# DUE_Shield.net
KiCad netlist of a schematic drawn in Altium Designer
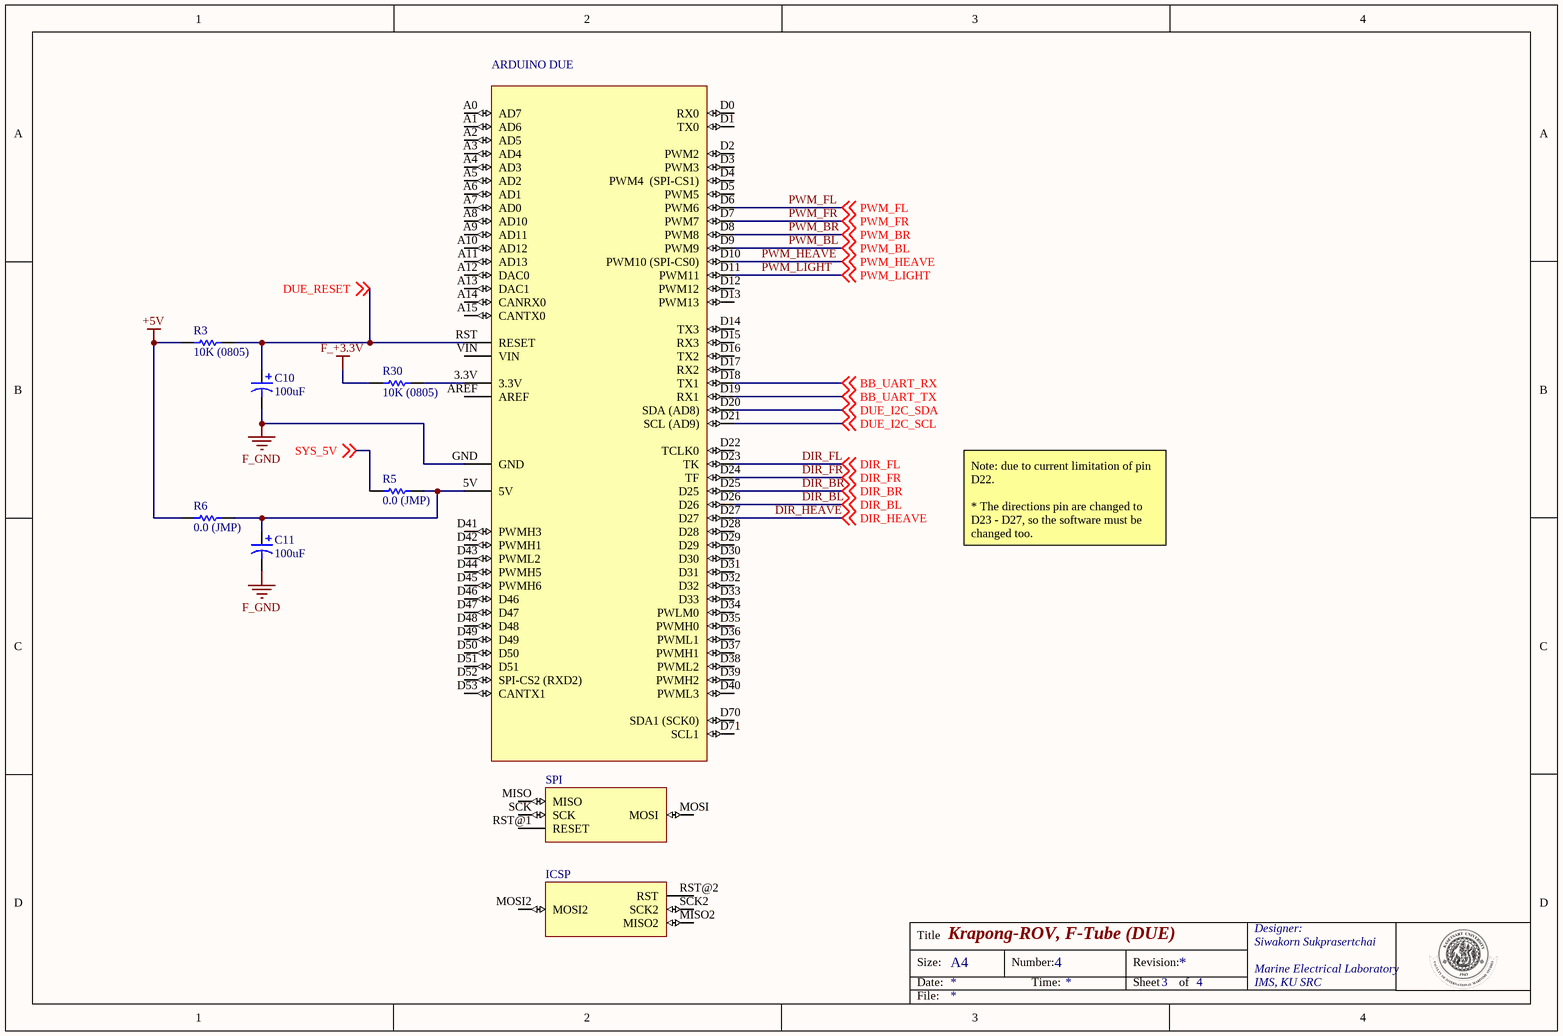
[diagram p0: DUE_Shield.SchDoc]

(export (version "E")
  (design (tool "Eeschema 10.0.6"))
  (components
    (comp (ref "C10")
      (value "100uF")
      (footprint "PCB-ec5i0bi6g8n3i6bd77c9-1")
      (description "WX Series 100 uF 25 V ±20 % Surface Mount Chip Aluminum Electrolytic Capacitor")
      (fields (field (name "MANUFACTURER PART NUMBER") "UWX1E101MCL1GB"))
      (libsource (lib "FavoritesLibrary") (part "SYM-42da8bd37ecc9d1d-1"))
    )
    (comp (ref "C11")
      (value "100uF")
      (footprint "PCB-ibkib54e90xysjsqnert-1")
      (description "Capacitor Alum Elec, 10uf, 100v, 20%, Capacitor Alum Elec, 10uf, 100v, 20%, Smd, Full Reel")
      (fields (field (name "MANUFACTURER PART NUMBER") "EEE-2AA100UP"))
      (libsource (lib "FavoritesLibrary") (part "SYM-da8810cd3d6e054f-1"))
    )
    (comp (ref "DUE")
      (value "arduino due schematic and base pcb to top")
      (footprint "PCB-973053-1")
      (description "ARDUINO DUE schematic and base pcb")
      (libsource (lib "CommunityVault") (part "CMP-973053-32"))
    )
    (comp (ref "R3")
      (value "10K (0805)")
      (footprint "RESC2013X60X40NL15T20")
      (description "RES SMD 10K OHM 1% 1/3W 0805")
      (libsource (lib "CommunityVault") (part "CMP-1860549-2"))
    )
    (comp (ref "R5")
      (value "0.0 (JMP)")
      (footprint "RESC2013X60X35ML10T20")
      (description "Res Thick Film 0805 0 Ohm Molded SMD Paper T/R")
      (fields (field (name "MANUFACTURER PART NUMBER") "RC0805FR-070RL"))
      (libsource (lib "FavoritesLibrary") (part "SYM-f3d13a5618eb2c16-1"))
    )
    (comp (ref "R6")
      (value "0.0 (JMP)")
      (footprint "RESC2013X60X35ML10T20")
      (description "Res Thick Film 0805 0 Ohm Molded SMD Paper T/R")
      (fields (field (name "MANUFACTURER PART NUMBER") "RC0805FR-070RL"))
      (libsource (lib "FavoritesLibrary") (part "SYM-f3d13a5618eb2c16-1"))
    )
    (comp (ref "R30")
      (value "10K (0805)")
      (footprint "RESC2013X60X40NL15T20")
      (description "RES SMD 10K OHM 1% 1/3W 0805")
      (libsource (lib "FavoritesLibrary") (part "RES-2"))
    )
  )
  (nets
    (net (code "1") (name "+5V") (class "Default")
      (node (ref "R3") (pin "1") (pinfunction "1_1") (pintype "passive"))
      (node (ref "R6") (pin "1") (pinfunction "1_1") (pintype "passive"))
    )
    (net (code "2") (name "BB_UART_RX") (class "Default")
      (node (ref "DUE") (pin "D18") (pinfunction "TX1_D18") (pintype "bidirectional"))
    )
    (net (code "3") (name "BB_UART_TX") (class "Default")
      (node (ref "DUE") (pin "D19") (pinfunction "RX1_D19") (pintype "bidirectional"))
    )
    (net (code "4") (name "DIR_BL") (class "Default")
      (node (ref "DUE") (pin "D26") (pinfunction "D26_D26") (pintype "bidirectional"))
    )
    (net (code "5") (name "DIR_BR") (class "Default")
      (node (ref "DUE") (pin "D25") (pinfunction "D25_D25") (pintype "bidirectional"))
    )
    (net (code "6") (name "DIR_FL") (class "Default")
      (node (ref "DUE") (pin "D23") (pinfunction "TK_D23") (pintype "bidirectional"))
    )
    (net (code "7") (name "DIR_FR") (class "Default")
      (node (ref "DUE") (pin "D24") (pinfunction "TF_D24") (pintype "bidirectional"))
    )
    (net (code "8") (name "DIR_HEAVE") (class "Default")
      (node (ref "DUE") (pin "D27") (pinfunction "D27_D27") (pintype "bidirectional"))
    )
    (net (code "9") (name "DUE_I2C_SCL") (class "Default")
      (node (ref "DUE") (pin "D21") (pinfunction "SCL_(AD9)_D21") (pintype "bidirectional"))
    )
    (net (code "10") (name "DUE_I2C_SDA") (class "Default")
      (node (ref "DUE") (pin "D20") (pinfunction "SDA_(AD8)_D20") (pintype "bidirectional"))
    )
    (net (code "11") (name "DUE_RESET") (class "Default")
      (node (ref "C10") (pin "1") (pinfunction "1_1") (pintype "passive"))
      (node (ref "DUE") (pin "RST") (pinfunction "RESET_RST") (pintype "passive"))
      (node (ref "R3") (pin "2") (pinfunction "2_2") (pintype "passive"))
    )
    (net (code "12") (name "F_+3.3V") (class "Default")
      (node (ref "R30") (pin "1") (pinfunction "1_1") (pintype "passive"))
    )
    (net (code "13") (name "F_GND") (class "Default")
      (node (ref "C10") (pin "2") (pinfunction "2_2") (pintype "passive"))
      (node (ref "C11") (pin "2") (pinfunction "2_2") (pintype "passive"))
      (node (ref "DUE") (pin "GND") (pinfunction "GND_GND") (pintype "power_in"))
    )
    (net (code "14") (name "Net-(C11-Pad1)") (class "Default")
      (node (ref "C11") (pin "1") (pinfunction "1_1") (pintype "passive"))
      (node (ref "DUE") (pin "5V") (pinfunction "5V_5V") (pintype "power_in"))
      (node (ref "R5") (pin "2") (pinfunction "2_2") (pintype "passive"))
      (node (ref "R6") (pin "2") (pinfunction "2_2") (pintype "passive"))
    )
    (net (code "15") (name "Net-(DUE-Pad3.3V)") (class "Default")
      (node (ref "DUE") (pin "3.3V") (pinfunction "3.3V_3.3V") (pintype "power_in"))
      (node (ref "R30") (pin "2") (pinfunction "2_2") (pintype "passive"))
    )
    (net (code "16") (name "PWM_BL") (class "Default")
      (node (ref "DUE") (pin "D9") (pinfunction "PWM9_D9") (pintype "bidirectional"))
    )
    (net (code "17") (name "PWM_BR") (class "Default")
      (node (ref "DUE") (pin "D8") (pinfunction "PWM8_D8") (pintype "bidirectional"))
    )
    (net (code "18") (name "PWM_FL") (class "Default")
      (node (ref "DUE") (pin "D6") (pinfunction "PWM6_D6") (pintype "bidirectional"))
    )
    (net (code "19") (name "PWM_FR") (class "Default")
      (node (ref "DUE") (pin "D7") (pinfunction "PWM7_D7") (pintype "bidirectional"))
    )
    (net (code "20") (name "PWM_HEAVE") (class "Default")
      (node (ref "DUE") (pin "D10") (pinfunction "PWM10_(SPI-CS0)_D10") (pintype "bidirectional"))
    )
    (net (code "21") (name "PWM_LIGHT") (class "Default")
      (node (ref "DUE") (pin "D11") (pinfunction "PWM11_D11") (pintype "bidirectional"))
    )
    (net (code "22") (name "SYS_5V") (class "Default")
      (node (ref "R5") (pin "1") (pinfunction "1_1") (pintype "passive"))
    )
    (net (code "23") (name "unconnected-(DUE-AD0-PadA7)") (class "Default")
      (node (ref "DUE") (pin "A7") (pinfunction "AD0_A7") (pintype "bidirectional"))
    )
    (net (code "24") (name "unconnected-(DUE-AD1-PadA6)") (class "Default")
      (node (ref "DUE") (pin "A6") (pinfunction "AD1_A6") (pintype "bidirectional"))
    )
    (net (code "25") (name "unconnected-(DUE-AD2-PadA5)") (class "Default")
      (node (ref "DUE") (pin "A5") (pinfunction "AD2_A5") (pintype "bidirectional"))
    )
    (net (code "26") (name "unconnected-(DUE-AD3-PadA4)") (class "Default")
      (node (ref "DUE") (pin "A4") (pinfunction "AD3_A4") (pintype "bidirectional"))
    )
    (net (code "27") (name "unconnected-(DUE-AD4-PadA3)") (class "Default")
      (node (ref "DUE") (pin "A3") (pinfunction "AD4_A3") (pintype "bidirectional"))
    )
    (net (code "28") (name "unconnected-(DUE-AD5-PadA2)") (class "Default")
      (node (ref "DUE") (pin "A2") (pinfunction "AD5_A2") (pintype "bidirectional"))
    )
    (net (code "29") (name "unconnected-(DUE-AD6-PadA1)") (class "Default")
      (node (ref "DUE") (pin "A1") (pinfunction "AD6_A1") (pintype "bidirectional"))
    )
    (net (code "30") (name "unconnected-(DUE-AD7-PadA0)") (class "Default")
      (node (ref "DUE") (pin "A0") (pinfunction "AD7_A0") (pintype "bidirectional"))
    )
    (net (code "31") (name "unconnected-(DUE-AD10-PadA8)") (class "Default")
      (node (ref "DUE") (pin "A8") (pinfunction "AD10_A8") (pintype "bidirectional"))
    )
    (net (code "32") (name "unconnected-(DUE-AD11-PadA9)") (class "Default")
      (node (ref "DUE") (pin "A9") (pinfunction "AD11_A9") (pintype "bidirectional"))
    )
    (net (code "33") (name "unconnected-(DUE-AD12-PadA10)") (class "Default")
      (node (ref "DUE") (pin "A10") (pinfunction "AD12_A10") (pintype "bidirectional"))
    )
    (net (code "34") (name "unconnected-(DUE-AD13-PadA11)") (class "Default")
      (node (ref "DUE") (pin "A11") (pinfunction "AD13_A11") (pintype "bidirectional"))
    )
    (net (code "35") (name "unconnected-(DUE-CANRX0-PadA14)") (class "Default")
      (node (ref "DUE") (pin "A14") (pinfunction "CANRX0_A14") (pintype "bidirectional"))
    )
    (net (code "36") (name "unconnected-(DUE-CANTX0-PadA15)") (class "Default")
      (node (ref "DUE") (pin "A15") (pinfunction "CANTX0_A15") (pintype "bidirectional"))
    )
    (net (code "37") (name "unconnected-(DUE-CANTX1-PadD53)") (class "Default")
      (node (ref "DUE") (pin "D53") (pinfunction "CANTX1_D53") (pintype "bidirectional"))
    )
    (net (code "38") (name "unconnected-(DUE-DAC0-PadA12)") (class "Default")
      (node (ref "DUE") (pin "A12") (pinfunction "DAC0_A12") (pintype "bidirectional"))
    )
    (net (code "39") (name "unconnected-(DUE-DAC1-PadA13)") (class "Default")
      (node (ref "DUE") (pin "A13") (pinfunction "DAC1_A13") (pintype "bidirectional"))
    )
    (net (code "40") (name "unconnected-(DUE-PWLM0-PadD34)") (class "Default")
      (node (ref "DUE") (pin "D34") (pinfunction "PWLM0_D34") (pintype "bidirectional"))
    )
    (net (code "41") (name "unconnected-(DUE-PWM2-PadD2)") (class "Default")
      (node (ref "DUE") (pin "D2") (pinfunction "PWM2_D2") (pintype "bidirectional"))
    )
    (net (code "42") (name "unconnected-(DUE-PWM3-PadD3)") (class "Default")
      (node (ref "DUE") (pin "D3") (pinfunction "PWM3_D3") (pintype "bidirectional"))
    )
    (net (code "43") (name "unconnected-(DUE-PWM4__(SPI-CS1)-PadD4)") (class "Default")
      (node (ref "DUE") (pin "D4") (pinfunction "PWM4__(SPI-CS1)_D4") (pintype "bidirectional"))
    )
    (net (code "44") (name "unconnected-(DUE-PWM5-PadD5)") (class "Default")
      (node (ref "DUE") (pin "D5") (pinfunction "PWM5_D5") (pintype "bidirectional"))
    )
    (net (code "45") (name "unconnected-(DUE-PWM12-PadD12)") (class "Default")
      (node (ref "DUE") (pin "D12") (pinfunction "PWM12_D12") (pintype "bidirectional"))
    )
    (net (code "46") (name "unconnected-(DUE-PWM13-PadD13)") (class "Default")
      (node (ref "DUE") (pin "D13") (pinfunction "PWM13_D13") (pintype "bidirectional"))
    )
    (net (code "47") (name "unconnected-(DUE-PWMH0-PadD35)") (class "Default")
      (node (ref "DUE") (pin "D35") (pinfunction "PWMH0_D35") (pintype "bidirectional"))
    )
    (net (code "48") (name "unconnected-(DUE-PWMH1-PadD37)") (class "Default")
      (node (ref "DUE") (pin "D37") (pinfunction "PWMH1_D37") (pintype "bidirectional"))
    )
    (net (code "49") (name "unconnected-(DUE-PWMH1-PadD42)") (class "Default")
      (node (ref "DUE") (pin "D42") (pinfunction "PWMH1_D42") (pintype "bidirectional"))
    )
    (net (code "50") (name "unconnected-(DUE-PWMH2-PadD39)") (class "Default")
      (node (ref "DUE") (pin "D39") (pinfunction "PWMH2_D39") (pintype "bidirectional"))
    )
    (net (code "51") (name "unconnected-(DUE-PWMH3-PadD41)") (class "Default")
      (node (ref "DUE") (pin "D41") (pinfunction "PWMH3_D41") (pintype "bidirectional"))
    )
    (net (code "52") (name "unconnected-(DUE-PWMH5-PadD44)") (class "Default")
      (node (ref "DUE") (pin "D44") (pinfunction "PWMH5_D44") (pintype "bidirectional"))
    )
    (net (code "53") (name "unconnected-(DUE-PWMH6-PadD45)") (class "Default")
      (node (ref "DUE") (pin "D45") (pinfunction "PWMH6_D45") (pintype "bidirectional"))
    )
    (net (code "54") (name "unconnected-(DUE-PWML1-PadD36)") (class "Default")
      (node (ref "DUE") (pin "D36") (pinfunction "PWML1_D36") (pintype "bidirectional"))
    )
    (net (code "55") (name "unconnected-(DUE-PWML2-PadD38)") (class "Default")
      (node (ref "DUE") (pin "D38") (pinfunction "PWML2_D38") (pintype "bidirectional"))
    )
    (net (code "56") (name "unconnected-(DUE-PWML2-PadD43)") (class "Default")
      (node (ref "DUE") (pin "D43") (pinfunction "PWML2_D43") (pintype "bidirectional"))
    )
    (net (code "57") (name "unconnected-(DUE-PWML3-PadD40)") (class "Default")
      (node (ref "DUE") (pin "D40") (pinfunction "PWML3_D40") (pintype "bidirectional"))
    )
    (net (code "58") (name "unconnected-(DUE-PadAREF)") (class "Default")
      (node (ref "DUE") (pin "AREF") (pinfunction "AREF_AREF") (pintype "power_in"))
    )
    (net (code "59") (name "unconnected-(DUE-PadD28)") (class "Default")
      (node (ref "DUE") (pin "D28") (pinfunction "D28_D28") (pintype "bidirectional"))
    )
    (net (code "60") (name "unconnected-(DUE-PadD29)") (class "Default")
      (node (ref "DUE") (pin "D29") (pinfunction "D29_D29") (pintype "bidirectional"))
    )
    (net (code "61") (name "unconnected-(DUE-PadD30)") (class "Default")
      (node (ref "DUE") (pin "D30") (pinfunction "D30_D30") (pintype "bidirectional"))
    )
    (net (code "62") (name "unconnected-(DUE-PadD31)") (class "Default")
      (node (ref "DUE") (pin "D31") (pinfunction "D31_D31") (pintype "bidirectional"))
    )
    (net (code "63") (name "unconnected-(DUE-PadD32)") (class "Default")
      (node (ref "DUE") (pin "D32") (pinfunction "D32_D32") (pintype "bidirectional"))
    )
    (net (code "64") (name "unconnected-(DUE-PadD33)") (class "Default")
      (node (ref "DUE") (pin "D33") (pinfunction "D33_D33") (pintype "bidirectional"))
    )
    (net (code "65") (name "unconnected-(DUE-PadD46)") (class "Default")
      (node (ref "DUE") (pin "D46") (pinfunction "D46_D46") (pintype "bidirectional"))
    )
    (net (code "66") (name "unconnected-(DUE-PadD47)") (class "Default")
      (node (ref "DUE") (pin "D47") (pinfunction "D47_D47") (pintype "bidirectional"))
    )
    (net (code "67") (name "unconnected-(DUE-PadD48)") (class "Default")
      (node (ref "DUE") (pin "D48") (pinfunction "D48_D48") (pintype "bidirectional"))
    )
    (net (code "68") (name "unconnected-(DUE-PadD49)") (class "Default")
      (node (ref "DUE") (pin "D49") (pinfunction "D49_D49") (pintype "bidirectional"))
    )
    (net (code "69") (name "unconnected-(DUE-PadD50)") (class "Default")
      (node (ref "DUE") (pin "D50") (pinfunction "D50_D50") (pintype "bidirectional"))
    )
    (net (code "70") (name "unconnected-(DUE-PadD51)") (class "Default")
      (node (ref "DUE") (pin "D51") (pinfunction "D51_D51") (pintype "bidirectional"))
    )
    (net (code "71") (name "unconnected-(DUE-PadMISO)") (class "Default")
      (node (ref "DUE") (pin "MISO") (pinfunction "MISO_MISO") (pintype "bidirectional"))
    )
    (net (code "72") (name "unconnected-(DUE-PadMISO2)") (class "Default")
      (node (ref "DUE") (pin "MISO2") (pinfunction "MISO2_MISO2") (pintype "bidirectional"))
    )
    (net (code "73") (name "unconnected-(DUE-PadMOSI)") (class "Default")
      (node (ref "DUE") (pin "MOSI") (pinfunction "MOSI_MOSI") (pintype "bidirectional"))
    )
    (net (code "74") (name "unconnected-(DUE-PadMOSI2)") (class "Default")
      (node (ref "DUE") (pin "MOSI2") (pinfunction "MOSI2_MOSI2") (pintype "bidirectional"))
    )
    (net (code "75") (name "unconnected-(DUE-PadSCK)") (class "Default")
      (node (ref "DUE") (pin "SCK") (pinfunction "SCK_SCK") (pintype "bidirectional"))
    )
    (net (code "76") (name "unconnected-(DUE-PadSCK2)") (class "Default")
      (node (ref "DUE") (pin "SCK2") (pinfunction "SCK2_SCK2") (pintype "bidirectional"))
    )
    (net (code "77") (name "unconnected-(DUE-PadVIN)") (class "Default")
      (node (ref "DUE") (pin "VIN") (pinfunction "VIN_VIN") (pintype "power_in"))
    )
    (net (code "78") (name "unconnected-(DUE-RESET-PadRST@1)") (class "Default")
      (node (ref "DUE") (pin "RST@1") (pinfunction "RESET_RST@1") (pintype "passive"))
    )
    (net (code "79") (name "unconnected-(DUE-RST-PadRST@2)") (class "Default")
      (node (ref "DUE") (pin "RST@2") (pinfunction "RST_RST@2") (pintype "passive"))
    )
    (net (code "80") (name "unconnected-(DUE-RX0-PadD0)") (class "Default")
      (node (ref "DUE") (pin "D0") (pinfunction "RX0_D0") (pintype "bidirectional"))
    )
    (net (code "81") (name "unconnected-(DUE-RX2-PadD17)") (class "Default")
      (node (ref "DUE") (pin "D17") (pinfunction "RX2_D17") (pintype "bidirectional"))
    )
    (net (code "82") (name "unconnected-(DUE-RX3-PadD15)") (class "Default")
      (node (ref "DUE") (pin "D15") (pinfunction "RX3_D15") (pintype "bidirectional"))
    )
    (net (code "83") (name "unconnected-(DUE-SCL1-PadD71)") (class "Default")
      (node (ref "DUE") (pin "D71") (pinfunction "SCL1_D71") (pintype "bidirectional"))
    )
    (net (code "84") (name "unconnected-(DUE-SDA1_(SCK0)-PadD70)") (class "Default")
      (node (ref "DUE") (pin "D70") (pinfunction "SDA1_(SCK0)_D70") (pintype "bidirectional"))
    )
    (net (code "85") (name "unconnected-(DUE-SPI-CS2_(RXD2)-PadD52)") (class "Default")
      (node (ref "DUE") (pin "D52") (pinfunction "SPI-CS2_(RXD2)_D52") (pintype "bidirectional"))
    )
    (net (code "86") (name "unconnected-(DUE-TCLK0-PadD22)") (class "Default")
      (node (ref "DUE") (pin "D22") (pinfunction "TCLK0_D22") (pintype "bidirectional"))
    )
    (net (code "87") (name "unconnected-(DUE-TX0-PadD1)") (class "Default")
      (node (ref "DUE") (pin "D1") (pinfunction "TX0_D1") (pintype "bidirectional"))
    )
    (net (code "88") (name "unconnected-(DUE-TX2-PadD16)") (class "Default")
      (node (ref "DUE") (pin "D16") (pinfunction "TX2_D16") (pintype "bidirectional"))
    )
    (net (code "89") (name "unconnected-(DUE-TX3-PadD14)") (class "Default")
      (node (ref "DUE") (pin "D14") (pinfunction "TX3_D14") (pintype "bidirectional"))
    )
  )
)
